# QFN12.net
KiCad netlist of a schematic drawn in EAGLE
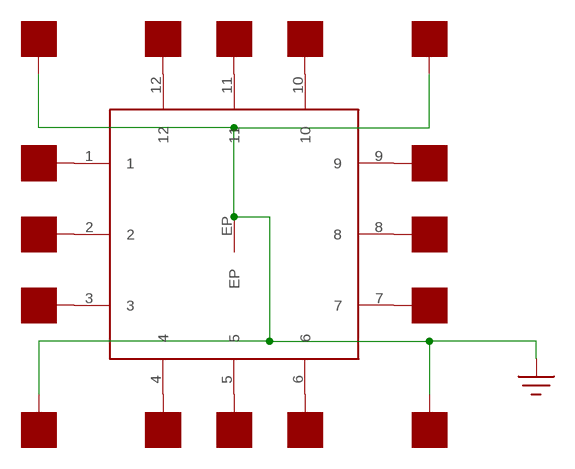
[diagram p0: schematic, sheet 1]

(export (version "E")
  (design (tool "Eeschema 10.0.6"))
  (components
    (comp (ref "U$1")
      (value "QFN12")
      (footprint "eagle-import:QFN12-3X3")
      (libsource (lib "eagle-import") (part "QFN12"))
    )
    (comp (ref "U$2")
      (value "PAD50MIL")
      (footprint "eagle-import:PAD_50MIL")
      (libsource (lib "eagle-import") (part "PAD50MIL"))
    )
    (comp (ref "U$3")
      (value "PAD50MIL")
      (footprint "eagle-import:PAD_50MIL")
      (libsource (lib "eagle-import") (part "PAD50MIL"))
    )
    (comp (ref "U$4")
      (value "PAD50MIL")
      (footprint "eagle-import:PAD_50MIL")
      (libsource (lib "eagle-import") (part "PAD50MIL"))
    )
    (comp (ref "U$5")
      (value "PAD50MIL")
      (footprint "eagle-import:PAD_50MIL")
      (libsource (lib "eagle-import") (part "PAD50MIL"))
    )
    (comp (ref "U$6")
      (value "PAD50MIL")
      (footprint "eagle-import:PAD_50MIL")
      (libsource (lib "eagle-import") (part "PAD50MIL"))
    )
    (comp (ref "U$7")
      (value "PAD50MIL")
      (footprint "eagle-import:PAD_50MIL")
      (libsource (lib "eagle-import") (part "PAD50MIL"))
    )
    (comp (ref "U$8")
      (value "PAD50MIL")
      (footprint "eagle-import:PAD_50MIL")
      (libsource (lib "eagle-import") (part "PAD50MIL"))
    )
    (comp (ref "U$9")
      (value "PAD50MIL")
      (footprint "eagle-import:PAD_50MIL")
      (libsource (lib "eagle-import") (part "PAD50MIL"))
    )
    (comp (ref "U$10")
      (value "PAD50MIL")
      (footprint "eagle-import:PAD_50MIL")
      (libsource (lib "eagle-import") (part "PAD50MIL"))
    )
    (comp (ref "U$11")
      (value "PAD50MIL")
      (footprint "eagle-import:PAD_50MIL")
      (libsource (lib "eagle-import") (part "PAD50MIL"))
    )
    (comp (ref "U$12")
      (value "PAD50MIL")
      (footprint "eagle-import:PAD_50MIL")
      (libsource (lib "eagle-import") (part "PAD50MIL"))
    )
    (comp (ref "U$13")
      (value "PAD50MIL")
      (footprint "eagle-import:PAD_50MIL")
      (libsource (lib "eagle-import") (part "PAD50MIL"))
    )
    (comp (ref "U$14")
      (value "PAD50MIL")
      (footprint "eagle-import:PAD_50MIL")
      (libsource (lib "eagle-import") (part "PAD50MIL"))
    )
    (comp (ref "U$15")
      (value "PAD50MIL")
      (footprint "eagle-import:PAD_50MIL")
      (libsource (lib "eagle-import") (part "PAD50MIL"))
    )
    (comp (ref "U$16")
      (value "PAD50MIL")
      (footprint "eagle-import:PAD_50MIL")
      (libsource (lib "eagle-import") (part "PAD50MIL"))
    )
    (comp (ref "U$17")
      (value "PAD50MIL")
      (footprint "eagle-import:PAD_50MIL")
      (libsource (lib "eagle-import") (part "PAD50MIL"))
    )
  )
  (nets
    (net (code "1") (name "GND") (class "Default")
      (node (ref "U$1") (pin "EP") (pinfunction "EP_EP") (pintype "bidirectional"))
      (node (ref "U$14") (pin "P$1") (pinfunction "P$1_P$1") (pintype "bidirectional"))
      (node (ref "U$15") (pin "P$1") (pinfunction "P$1_P$1") (pintype "bidirectional"))
      (node (ref "U$16") (pin "P$1") (pinfunction "P$1_P$1") (pintype "bidirectional"))
      (node (ref "U$17") (pin "P$1") (pinfunction "P$1_P$1") (pintype "bidirectional"))
    )
    (net (code "2") (name "Net-(U$1-Pad1)") (class "Default")
      (node (ref "U$1") (pin "1") (pinfunction "1_1") (pintype "bidirectional"))
      (node (ref "U$8") (pin "P$1") (pinfunction "P$1_P$1") (pintype "bidirectional"))
    )
    (net (code "3") (name "Net-(U$1-Pad2)") (class "Default")
      (node (ref "U$1") (pin "2") (pinfunction "2_2") (pintype "bidirectional"))
      (node (ref "U$9") (pin "P$1") (pinfunction "P$1_P$1") (pintype "bidirectional"))
    )
    (net (code "4") (name "Net-(U$1-Pad3)") (class "Default")
      (node (ref "U$1") (pin "3") (pinfunction "3_3") (pintype "bidirectional"))
      (node (ref "U$10") (pin "P$1") (pinfunction "P$1_P$1") (pintype "bidirectional"))
    )
    (net (code "5") (name "Net-(U$1-Pad4)") (class "Default")
      (node (ref "U$1") (pin "4") (pinfunction "4_4") (pintype "bidirectional"))
      (node (ref "U$11") (pin "P$1") (pinfunction "P$1_P$1") (pintype "bidirectional"))
    )
    (net (code "6") (name "Net-(U$1-Pad5)") (class "Default")
      (node (ref "U$1") (pin "5") (pinfunction "5_5") (pintype "bidirectional"))
      (node (ref "U$12") (pin "P$1") (pinfunction "P$1_P$1") (pintype "bidirectional"))
    )
    (net (code "7") (name "Net-(U$1-Pad6)") (class "Default")
      (node (ref "U$1") (pin "6") (pinfunction "6_6") (pintype "bidirectional"))
      (node (ref "U$13") (pin "P$1") (pinfunction "P$1_P$1") (pintype "bidirectional"))
    )
    (net (code "8") (name "Net-(U$1-Pad7)") (class "Default")
      (node (ref "U$1") (pin "7") (pinfunction "7_7") (pintype "bidirectional"))
      (node (ref "U$4") (pin "P$1") (pinfunction "P$1_P$1") (pintype "bidirectional"))
    )
    (net (code "9") (name "Net-(U$1-Pad8)") (class "Default")
      (node (ref "U$1") (pin "8") (pinfunction "8_8") (pintype "bidirectional"))
      (node (ref "U$3") (pin "P$1") (pinfunction "P$1_P$1") (pintype "bidirectional"))
    )
    (net (code "10") (name "Net-(U$1-Pad9)") (class "Default")
      (node (ref "U$1") (pin "9") (pinfunction "9_9") (pintype "bidirectional"))
      (node (ref "U$2") (pin "P$1") (pinfunction "P$1_P$1") (pintype "bidirectional"))
    )
    (net (code "11") (name "Net-(U$1-Pad10)") (class "Default")
      (node (ref "U$1") (pin "10") (pinfunction "10_10") (pintype "bidirectional"))
      (node (ref "U$5") (pin "P$1") (pinfunction "P$1_P$1") (pintype "bidirectional"))
    )
    (net (code "12") (name "Net-(U$1-Pad11)") (class "Default")
      (node (ref "U$1") (pin "11") (pinfunction "11_11") (pintype "bidirectional"))
      (node (ref "U$6") (pin "P$1") (pinfunction "P$1_P$1") (pintype "bidirectional"))
    )
    (net (code "13") (name "Net-(U$1-Pad12)") (class "Default")
      (node (ref "U$1") (pin "12") (pinfunction "12_12") (pintype "bidirectional"))
      (node (ref "U$7") (pin "P$1") (pinfunction "P$1_P$1") (pintype "bidirectional"))
    )
  )
)
